# RF_AMP_1W.net
KiCad netlist of a schematic drawn in EAGLE
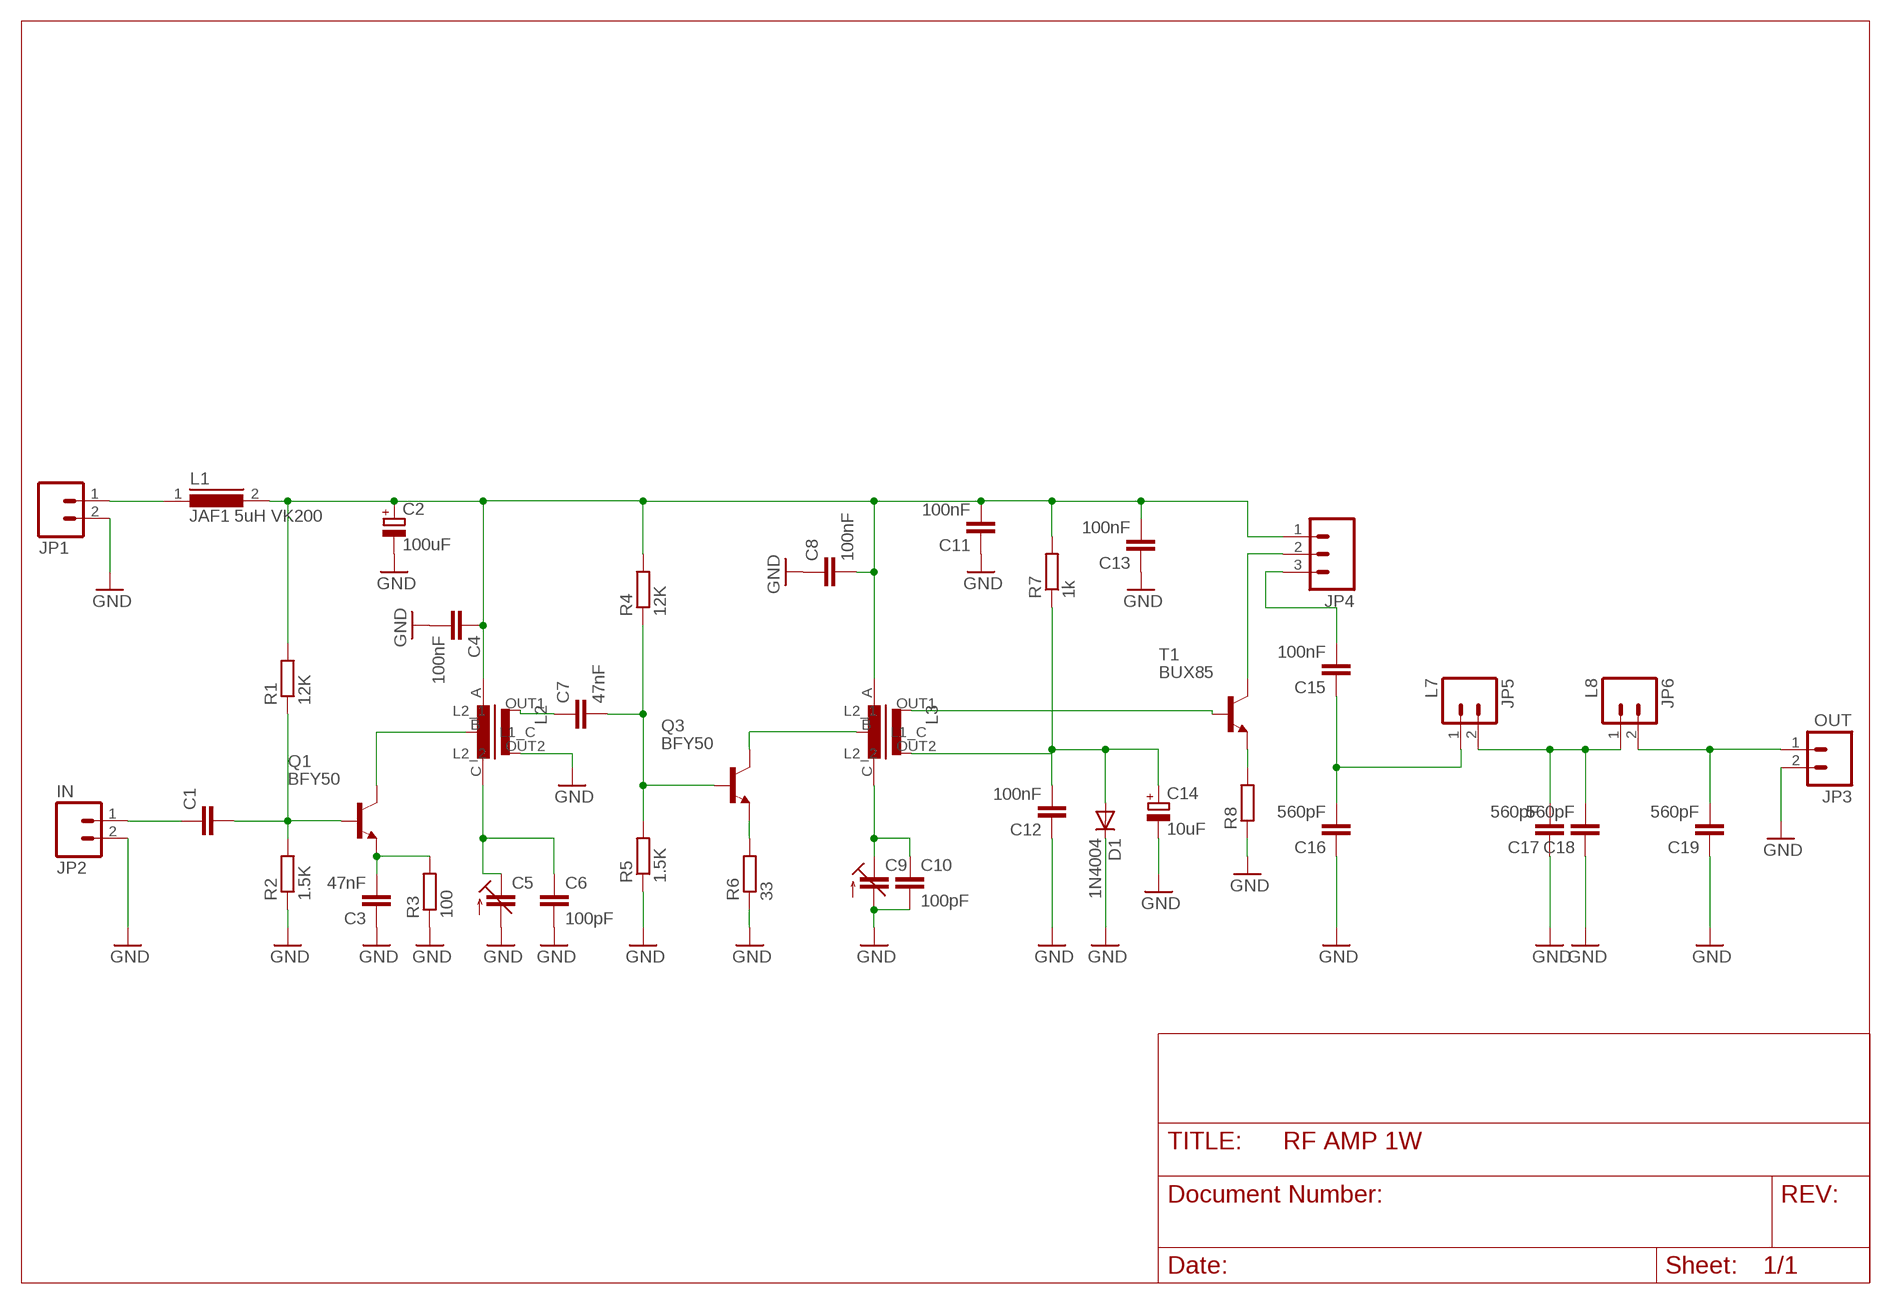
[diagram p0: schematic, sheet 1]

(export (version "E")
  (design (tool "Eeschema 10.0.6"))
  (components
    (comp (ref "C1")
      (value "C-EU025-025X050")
      (footprint "eagle-import:C025-025X050")
      (libsource (lib "eagle-import") (part "C-EU025-025X050"))
    )
    (comp (ref "C2")
      (value "100uF")
      (footprint "eagle-import:E2-5")
      (libsource (lib "eagle-import") (part "CPOL-EUE2-5"))
    )
    (comp (ref "C3")
      (value "47nF")
      (footprint "eagle-import:C025-025X050")
      (libsource (lib "eagle-import") (part "C-EU025-025X050"))
    )
    (comp (ref "C4")
      (value "100nF")
      (footprint "eagle-import:C025-025X050")
      (libsource (lib "eagle-import") (part "C-EU025-025X050"))
    )
    (comp (ref "C5")
      (value "C-TRIMM808")
      (footprint "eagle-import:CTRIM808-BC")
      (libsource (lib "eagle-import") (part "C-TRIMM808"))
    )
    (comp (ref "C6")
      (value "100pF")
      (footprint "eagle-import:C025-025X050")
      (libsource (lib "eagle-import") (part "C-EU025-025X050"))
    )
    (comp (ref "C7")
      (value "47nF")
      (footprint "eagle-import:C025-025X050")
      (libsource (lib "eagle-import") (part "C-EU025-025X050"))
    )
    (comp (ref "C8")
      (value "100nF")
      (footprint "eagle-import:C025-025X050")
      (libsource (lib "eagle-import") (part "C-EU025-025X050"))
    )
    (comp (ref "C9")
      (value "C-TRIMM808")
      (footprint "eagle-import:CTRIM808-BC")
      (libsource (lib "eagle-import") (part "C-TRIMM808"))
    )
    (comp (ref "C10")
      (value "100pF")
      (footprint "eagle-import:C025-025X050")
      (libsource (lib "eagle-import") (part "C-EU025-025X050"))
    )
    (comp (ref "C11")
      (value "100nF")
      (footprint "eagle-import:C025-025X050")
      (libsource (lib "eagle-import") (part "C-EU025-025X050"))
    )
    (comp (ref "C12")
      (value "100nF")
      (footprint "eagle-import:C025-025X050")
      (libsource (lib "eagle-import") (part "C-EU025-025X050"))
    )
    (comp (ref "C13")
      (value "100nF")
      (footprint "eagle-import:C025-025X050")
      (libsource (lib "eagle-import") (part "C-EU025-025X050"))
    )
    (comp (ref "C14")
      (value "10uF")
      (footprint "eagle-import:E2-5")
      (libsource (lib "eagle-import") (part "CPOL-EUE2-5"))
    )
    (comp (ref "C15")
      (value "100nF")
      (footprint "eagle-import:C025-025X050")
      (libsource (lib "eagle-import") (part "C-EU025-025X050"))
    )
    (comp (ref "C16")
      (value "560pF")
      (footprint "eagle-import:C025-025X050")
      (libsource (lib "eagle-import") (part "C-EU025-025X050"))
    )
    (comp (ref "C17")
      (value "560pF")
      (footprint "eagle-import:C025-025X050")
      (libsource (lib "eagle-import") (part "C-EU025-025X050"))
    )
    (comp (ref "C18")
      (value "560pF")
      (footprint "eagle-import:C025-025X050")
      (libsource (lib "eagle-import") (part "C-EU025-025X050"))
    )
    (comp (ref "C19")
      (value "560pF")
      (footprint "eagle-import:C025-025X050")
      (libsource (lib "eagle-import") (part "C-EU025-025X050"))
    )
    (comp (ref "D1")
      (value "1N4004")
      (footprint "eagle-import:DO41-10")
      (libsource (lib "eagle-import") (part "1N4004"))
    )
    (comp (ref "JP1")
      (value "M023.5MM")
      (footprint "eagle-import:SCREWTERMINAL-3.5MM-2")
      (libsource (lib "eagle-import") (part "M023.5MM"))
    )
    (comp (ref "JP2")
      (value "IN")
      (footprint "eagle-import:SCREWTERMINAL-3.5MM-2")
      (libsource (lib "eagle-import") (part "M023.5MM"))
    )
    (comp (ref "JP3")
      (value "OUT")
      (footprint "eagle-import:SCREWTERMINAL-3.5MM-2")
      (libsource (lib "eagle-import") (part "M023.5MM"))
    )
    (comp (ref "JP4")
      (value "M03-SCREW-5MM")
      (footprint "eagle-import:SCREWTERMINAL-5MM-3")
      (libsource (lib "eagle-import") (part "M03-SCREW-5MM"))
    )
    (comp (ref "JP5")
      (value "L7")
      (footprint "eagle-import:SCREWTERMINAL-5MM-2")
      (libsource (lib "eagle-import") (part "M025MM"))
    )
    (comp (ref "JP6")
      (value "L8")
      (footprint "eagle-import:SCREWTERMINAL-5MM-2")
      (libsource (lib "eagle-import") (part "M025MM"))
    )
    (comp (ref "L1")
      (value "JAF1 5uH VK200")
      (footprint "eagle-import:82114A")
      (libsource (lib "eagle-import") (part "82114A"))
    )
    (comp (ref "L2")
      (value "ED16")
      (footprint "eagle-import:ED16")
      (libsource (lib "eagle-import") (part "ED16"))
    )
    (comp (ref "L3")
      (value "ED16")
      (footprint "eagle-import:ED16")
      (libsource (lib "eagle-import") (part "ED16"))
    )
    (comp (ref "Q1")
      (value "BFY50")
      (footprint "eagle-import:TO39")
      (libsource (lib "eagle-import") (part "BFY50"))
    )
    (comp (ref "Q3")
      (value "BFY50")
      (footprint "eagle-import:TO39")
      (libsource (lib "eagle-import") (part "BFY50"))
    )
    (comp (ref "R1")
      (value "12K")
      (footprint "eagle-import:0207_10")
      (libsource (lib "eagle-import") (part "R-EU_0207/10"))
    )
    (comp (ref "R2")
      (value "1.5K")
      (footprint "eagle-import:0207_10")
      (libsource (lib "eagle-import") (part "R-EU_0207/10"))
    )
    (comp (ref "R3")
      (value "100")
      (footprint "eagle-import:0207_10")
      (libsource (lib "eagle-import") (part "R-EU_0207/10"))
    )
    (comp (ref "R4")
      (value "12K")
      (footprint "eagle-import:0207_10")
      (libsource (lib "eagle-import") (part "R-EU_0207/10"))
    )
    (comp (ref "R5")
      (value "1.5K")
      (footprint "eagle-import:0207_10")
      (libsource (lib "eagle-import") (part "R-EU_0207/10"))
    )
    (comp (ref "R6")
      (value "33")
      (footprint "eagle-import:0207_10")
      (libsource (lib "eagle-import") (part "R-EU_0207/10"))
    )
    (comp (ref "R7")
      (value "1k")
      (footprint "eagle-import:0207_10")
      (libsource (lib "eagle-import") (part "R-EU_0207/10"))
    )
    (comp (ref "R8")
      (value "R-EU_0207/12")
      (footprint "eagle-import:0207_12")
      (libsource (lib "eagle-import") (part "R-EU_0207/12"))
    )
    (comp (ref "T1")
      (value "BUX85")
      (footprint "eagle-import:TO220")
      (libsource (lib "eagle-import") (part "BUX85"))
    )
  )
  (nets
    (net (code "1") (name "GND") (class "Default")
      (node (ref "C10") (pin "2") (pinfunction "2_2") (pintype "passive"))
      (node (ref "C11") (pin "1") (pinfunction "1_1") (pintype "passive"))
      (node (ref "C12") (pin "1") (pinfunction "1_1") (pintype "passive"))
      (node (ref "C13") (pin "1") (pinfunction "1_1") (pintype "passive"))
      (node (ref "C14") (pin "-") (pinfunction "-_-") (pintype "passive"))
      (node (ref "C16") (pin "1") (pinfunction "1_1") (pintype "passive"))
      (node (ref "C17") (pin "1") (pinfunction "1_1") (pintype "passive"))
      (node (ref "C18") (pin "1") (pinfunction "1_1") (pintype "passive"))
      (node (ref "C19") (pin "1") (pinfunction "1_1") (pintype "passive"))
      (node (ref "C2") (pin "-") (pinfunction "-_-") (pintype "passive"))
      (node (ref "C3") (pin "1") (pinfunction "1_1") (pintype "passive"))
      (node (ref "C4") (pin "2") (pinfunction "2_2") (pintype "passive"))
      (node (ref "C5") (pin "2") (pinfunction "A_2") (pintype "passive"))
      (node (ref "C6") (pin "2") (pinfunction "2_2") (pintype "passive"))
      (node (ref "C8") (pin "1") (pinfunction "1_1") (pintype "passive"))
      (node (ref "C9") (pin "2") (pinfunction "A_2") (pintype "passive"))
      (node (ref "D1") (pin "C") (pinfunction "C_C") (pintype "passive"))
      (node (ref "JP1") (pin "2") (pinfunction "2_2") (pintype "passive"))
      (node (ref "JP2") (pin "2") (pinfunction "2_2") (pintype "passive"))
      (node (ref "JP3") (pin "2") (pinfunction "2_2") (pintype "passive"))
      (node (ref "L2") (pin "OUT2") (pinfunction "L2_2_OUT2") (pintype "bidirectional"))
      (node (ref "R2") (pin "1") (pinfunction "1_1") (pintype "passive"))
      (node (ref "R3") (pin "1") (pinfunction "1_1") (pintype "passive"))
      (node (ref "R5") (pin "1") (pinfunction "1_1") (pintype "passive"))
      (node (ref "R6") (pin "1") (pinfunction "1_1") (pintype "passive"))
      (node (ref "R8") (pin "1") (pinfunction "1_1") (pintype "passive"))
    )
    (net (code "2") (name "Net-(C1-Pad1)") (class "Default")
      (node (ref "C1") (pin "1") (pinfunction "1_1") (pintype "passive"))
      (node (ref "JP2") (pin "1") (pinfunction "1_1") (pintype "passive"))
    )
    (net (code "3") (name "Net-(C5-E)") (class "Default")
      (node (ref "C5") (pin "1") (pinfunction "E_1") (pintype "passive"))
      (node (ref "C6") (pin "1") (pinfunction "1_1") (pintype "passive"))
      (node (ref "L2") (pin "C") (pinfunction "L1_2_C") (pintype "passive"))
    )
    (net (code "4") (name "Net-(C9-E)") (class "Default")
      (node (ref "C10") (pin "1") (pinfunction "1_1") (pintype "passive"))
      (node (ref "C9") (pin "1") (pinfunction "E_1") (pintype "passive"))
      (node (ref "L3") (pin "C") (pinfunction "L1_2_C") (pintype "passive"))
    )
    (net (code "5") (name "Net-(C15-Pad1)") (class "Default")
      (node (ref "C15") (pin "1") (pinfunction "1_1") (pintype "passive"))
      (node (ref "C16") (pin "2") (pinfunction "2_2") (pintype "passive"))
      (node (ref "JP5") (pin "1") (pinfunction "1_1") (pintype "passive"))
    )
    (net (code "6") (name "Net-(C15-Pad2)") (class "Default")
      (node (ref "C15") (pin "2") (pinfunction "2_2") (pintype "passive"))
      (node (ref "JP4") (pin "3") (pinfunction "3_3") (pintype "passive"))
    )
    (net (code "7") (name "Net-(C17-Pad2)") (class "Default")
      (node (ref "C17") (pin "2") (pinfunction "2_2") (pintype "passive"))
      (node (ref "C18") (pin "2") (pinfunction "2_2") (pintype "passive"))
      (node (ref "JP5") (pin "2") (pinfunction "2_2") (pintype "passive"))
      (node (ref "JP6") (pin "1") (pinfunction "1_1") (pintype "passive"))
    )
    (net (code "8") (name "Net-(C19-Pad2)") (class "Default")
      (node (ref "C19") (pin "2") (pinfunction "2_2") (pintype "passive"))
      (node (ref "JP3") (pin "1") (pinfunction "1_1") (pintype "passive"))
      (node (ref "JP6") (pin "2") (pinfunction "2_2") (pintype "passive"))
    )
    (net (code "9") (name "Net-(JP1-Pad1)") (class "Default")
      (node (ref "JP1") (pin "1") (pinfunction "1_1") (pintype "passive"))
      (node (ref "L1") (pin "1") (pinfunction "1_1") (pintype "passive"))
    )
    (net (code "10") (name "Net-(L2-L1_1)") (class "Default")
      (node (ref "C11") (pin "2") (pinfunction "2_2") (pintype "passive"))
      (node (ref "C13") (pin "2") (pinfunction "2_2") (pintype "passive"))
      (node (ref "C2") (pin "+") (pinfunction "+_+") (pintype "passive"))
      (node (ref "C4") (pin "1") (pinfunction "1_1") (pintype "passive"))
      (node (ref "C8") (pin "2") (pinfunction "2_2") (pintype "passive"))
      (node (ref "JP4") (pin "1") (pinfunction "1_1") (pintype "passive"))
      (node (ref "L1") (pin "2") (pinfunction "2_2") (pintype "passive"))
      (node (ref "L2") (pin "A") (pinfunction "L1_1_A") (pintype "passive"))
      (node (ref "L3") (pin "A") (pinfunction "L1_1_A") (pintype "passive"))
      (node (ref "R1") (pin "2") (pinfunction "2_2") (pintype "passive"))
      (node (ref "R4") (pin "2") (pinfunction "2_2") (pintype "passive"))
      (node (ref "R7") (pin "2") (pinfunction "2_2") (pintype "passive"))
    )
    (net (code "11") (name "Net-(L2-L1_C)") (class "Default")
      (node (ref "L2") (pin "B") (pinfunction "L1_C_B") (pintype "bidirectional"))
      (node (ref "Q1") (pin "3") (pinfunction "C_3") (pintype "passive"))
    )
    (net (code "12") (name "Net-(L2-L2_1)") (class "Default")
      (node (ref "C7") (pin "1") (pinfunction "1_1") (pintype "passive"))
      (node (ref "L2") (pin "OUT1") (pinfunction "L2_1_OUT1") (pintype "bidirectional"))
    )
    (net (code "13") (name "Net-(L3-L1_C)") (class "Default")
      (node (ref "L3") (pin "B") (pinfunction "L1_C_B") (pintype "bidirectional"))
      (node (ref "Q3") (pin "3") (pinfunction "C_3") (pintype "passive"))
    )
    (net (code "14") (name "Net-(L3-L2_1)") (class "Default")
      (node (ref "L3") (pin "OUT1") (pinfunction "L2_1_OUT1") (pintype "bidirectional"))
      (node (ref "T1") (pin "1") (pinfunction "B_1") (pintype "passive"))
    )
    (net (code "15") (name "Net-(L3-L2_2)") (class "Default")
      (node (ref "C12") (pin "2") (pinfunction "2_2") (pintype "passive"))
      (node (ref "C14") (pin "+") (pinfunction "+_+") (pintype "passive"))
      (node (ref "D1") (pin "A") (pinfunction "A_A") (pintype "passive"))
      (node (ref "L3") (pin "OUT2") (pinfunction "L2_2_OUT2") (pintype "bidirectional"))
      (node (ref "R7") (pin "1") (pinfunction "1_1") (pintype "passive"))
    )
    (net (code "16") (name "Net-(Q1-B)") (class "Default")
      (node (ref "C1") (pin "2") (pinfunction "2_2") (pintype "passive"))
      (node (ref "Q1") (pin "2") (pinfunction "B_2") (pintype "passive"))
      (node (ref "R1") (pin "1") (pinfunction "1_1") (pintype "passive"))
      (node (ref "R2") (pin "2") (pinfunction "2_2") (pintype "passive"))
    )
    (net (code "17") (name "Net-(Q1-E)") (class "Default")
      (node (ref "C3") (pin "2") (pinfunction "2_2") (pintype "passive"))
      (node (ref "Q1") (pin "1") (pinfunction "E_1") (pintype "passive"))
      (node (ref "R3") (pin "2") (pinfunction "2_2") (pintype "passive"))
    )
    (net (code "18") (name "Net-(Q3-B)") (class "Default")
      (node (ref "C7") (pin "2") (pinfunction "2_2") (pintype "passive"))
      (node (ref "Q3") (pin "2") (pinfunction "B_2") (pintype "passive"))
      (node (ref "R4") (pin "1") (pinfunction "1_1") (pintype "passive"))
      (node (ref "R5") (pin "2") (pinfunction "2_2") (pintype "passive"))
    )
    (net (code "19") (name "Net-(Q3-E)") (class "Default")
      (node (ref "Q3") (pin "1") (pinfunction "E_1") (pintype "passive"))
      (node (ref "R6") (pin "2") (pinfunction "2_2") (pintype "passive"))
    )
    (net (code "20") (name "Net-(T1-C)") (class "Default")
      (node (ref "JP4") (pin "2") (pinfunction "2_2") (pintype "passive"))
      (node (ref "T1") (pin "2") (pinfunction "C_2") (pintype "passive"))
    )
    (net (code "21") (name "Net-(T1-E)") (class "Default")
      (node (ref "R8") (pin "2") (pinfunction "2_2") (pintype "passive"))
      (node (ref "T1") (pin "3") (pinfunction "E_3") (pintype "passive"))
    )
  )
)
